# symbol.net
KiCad netlist of a schematic drawn in Altium Designer
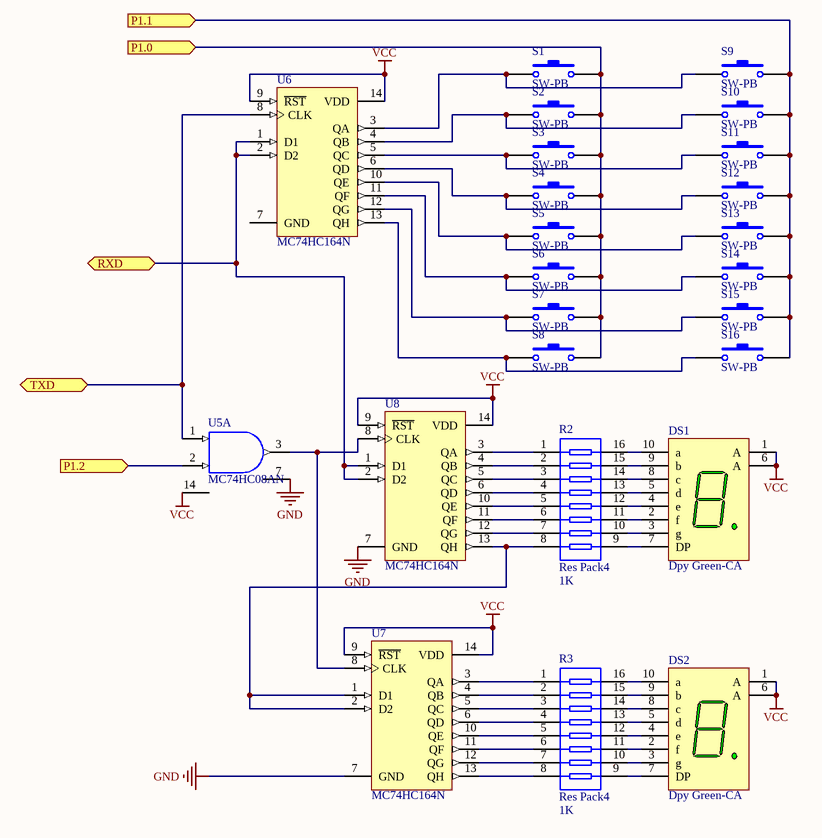
[diagram p0: 显示及键盘电路symbol.SchDoc]

(export (version "E")
  (design (tool "Eeschema 10.0.6"))
  (components
    (comp (ref "DS1")
      (value "Dpy Green-CA")
      (footprint "A")
      (description "7.62 mm Black Surface Green 7-Segment Display: CA, RH DP")
      (fields (field (name "PUBLISHER") "Altium Limited"))
      (libsource (lib "Miscellaneous Devices") (part "Dpy Green-CA"))
    )
    (comp (ref "DS2")
      (value "Dpy Green-CA")
      (footprint "A")
      (description "7.62 mm Black Surface Green 7-Segment Display: CA, RH DP")
      (fields (field (name "PUBLISHER") "Altium Limited"))
      (libsource (lib "Miscellaneous Devices") (part "Dpy Green-CA"))
    )
    (comp (ref "R2")
      (value "Res Pack4")
      (footprint "SSOP16_N")
      (description "Isolated Resistor Network")
      (fields (field (name "ALTIUM_VALUE") "1K") (field (name "PUBLISHER") "Altium Limited"))
      (libsource (lib "Miscellaneous Devices") (part "Res Pack4"))
    )
    (comp (ref "R3")
      (value "Res Pack4")
      (footprint "SSOP16_N")
      (description "Isolated Resistor Network")
      (fields (field (name "ALTIUM_VALUE") "1K") (field (name "PUBLISHER") "Altium Limited"))
      (libsource (lib "Miscellaneous Devices") (part "Res Pack4"))
    )
    (comp (ref "S1")
      (value "SW-PB")
      (footprint "SPST-2")
      (description "Switch")
      (fields (field (name "PUBLISHER") "Altium Limited"))
      (libsource (lib "Miscellaneous Devices") (part "SW-PB"))
    )
    (comp (ref "S2")
      (value "SW-PB")
      (footprint "SPST-2")
      (description "Switch")
      (fields (field (name "PUBLISHER") "Altium Limited"))
      (libsource (lib "Miscellaneous Devices") (part "SW-PB"))
    )
    (comp (ref "S3")
      (value "SW-PB")
      (footprint "SPST-2")
      (description "Switch")
      (fields (field (name "PUBLISHER") "Altium Limited"))
      (libsource (lib "Miscellaneous Devices") (part "SW-PB"))
    )
    (comp (ref "S4")
      (value "SW-PB")
      (footprint "SPST-2")
      (description "Switch")
      (fields (field (name "PUBLISHER") "Altium Limited"))
      (libsource (lib "Miscellaneous Devices") (part "SW-PB"))
    )
    (comp (ref "S5")
      (value "SW-PB")
      (footprint "SPST-2")
      (description "Switch")
      (fields (field (name "PUBLISHER") "Altium Limited"))
      (libsource (lib "Miscellaneous Devices") (part "SW-PB"))
    )
    (comp (ref "S6")
      (value "SW-PB")
      (footprint "SPST-2")
      (description "Switch")
      (fields (field (name "PUBLISHER") "Altium Limited"))
      (libsource (lib "Miscellaneous Devices") (part "SW-PB"))
    )
    (comp (ref "S7")
      (value "SW-PB")
      (footprint "SPST-2")
      (description "Switch")
      (fields (field (name "PUBLISHER") "Altium Limited"))
      (libsource (lib "Miscellaneous Devices") (part "SW-PB"))
    )
    (comp (ref "S8")
      (value "SW-PB")
      (footprint "SPST-2")
      (description "Switch")
      (fields (field (name "PUBLISHER") "Altium Limited"))
      (libsource (lib "Miscellaneous Devices") (part "SW-PB"))
    )
    (comp (ref "S9")
      (value "SW-PB")
      (footprint "SPST-2")
      (description "Switch")
      (fields (field (name "PUBLISHER") "Altium Limited"))
      (libsource (lib "Miscellaneous Devices") (part "SW-PB"))
    )
    (comp (ref "S10")
      (value "SW-PB")
      (footprint "SPST-2")
      (description "Switch")
      (fields (field (name "PUBLISHER") "Altium Limited"))
      (libsource (lib "Miscellaneous Devices") (part "SW-PB"))
    )
    (comp (ref "S11")
      (value "SW-PB")
      (footprint "SPST-2")
      (description "Switch")
      (fields (field (name "PUBLISHER") "Altium Limited"))
      (libsource (lib "Miscellaneous Devices") (part "SW-PB"))
    )
    (comp (ref "S12")
      (value "SW-PB")
      (footprint "SPST-2")
      (description "Switch")
      (fields (field (name "PUBLISHER") "Altium Limited"))
      (libsource (lib "Miscellaneous Devices") (part "SW-PB"))
    )
    (comp (ref "S13")
      (value "SW-PB")
      (footprint "SPST-2")
      (description "Switch")
      (fields (field (name "PUBLISHER") "Altium Limited"))
      (libsource (lib "Miscellaneous Devices") (part "SW-PB"))
    )
    (comp (ref "S14")
      (value "SW-PB")
      (footprint "SPST-2")
      (description "Switch")
      (fields (field (name "PUBLISHER") "Altium Limited"))
      (libsource (lib "Miscellaneous Devices") (part "SW-PB"))
    )
    (comp (ref "S15")
      (value "SW-PB")
      (footprint "SPST-2")
      (description "Switch")
      (fields (field (name "PUBLISHER") "Altium Limited"))
      (libsource (lib "Miscellaneous Devices") (part "SW-PB"))
    )
    (comp (ref "S16")
      (value "SW-PB")
      (footprint "SPST-2")
      (description "Switch")
      (fields (field (name "PUBLISHER") "Altium Limited"))
      (libsource (lib "Miscellaneous Devices") (part "SW-PB"))
    )
    (comp (ref "U5")
      (value "MC74HC08AN")
      (footprint "646-06")
      (description "Quad 2-Input AND Gate")
      (fields (field (name "PUBLISHER") "Altium Limited"))
      (libsource (lib "Motorola Logic Gate") (part "MC74HC08AN"))
    )
    (comp (ref "U6")
      (value "MC74HC164N")
      (footprint "646-06")
      (description "8-Bit Serial-Input/Parallel-Output Shift Register")
      (fields (field (name "PUBLISHER") "Altium Limited"))
      (libsource (lib "Motorola Logic Register") (part "MC74HC164N"))
    )
    (comp (ref "U7")
      (value "MC74HC164N")
      (footprint "646-06")
      (description "8-Bit Serial-Input/Parallel-Output Shift Register")
      (fields (field (name "PUBLISHER") "Altium Limited"))
      (libsource (lib "Motorola Logic Register") (part "MC74HC164N"))
    )
    (comp (ref "U8")
      (value "MC74HC164N")
      (footprint "646-06")
      (description "8-Bit Serial-Input/Parallel-Output Shift Register")
      (fields (field (name "PUBLISHER") "Altium Limited"))
      (libsource (lib "Motorola Logic Register") (part "MC74HC164N"))
    )
  )
  (nets
    (net (code "1") (name "/P1.0") (class "Default")
      (node (ref "S1") (pin "2") (pinfunction "2_2") (pintype "passive"))
      (node (ref "S2") (pin "2") (pinfunction "2_2") (pintype "passive"))
      (node (ref "S3") (pin "2") (pinfunction "2_2") (pintype "passive"))
      (node (ref "S4") (pin "2") (pinfunction "2_2") (pintype "passive"))
      (node (ref "S5") (pin "2") (pinfunction "2_2") (pintype "passive"))
      (node (ref "S6") (pin "2") (pinfunction "2_2") (pintype "passive"))
      (node (ref "S7") (pin "2") (pinfunction "2_2") (pintype "passive"))
      (node (ref "S8") (pin "2") (pinfunction "2_2") (pintype "passive"))
    )
    (net (code "2") (name "/P1.1") (class "Default")
      (node (ref "S10") (pin "2") (pinfunction "2_2") (pintype "passive"))
      (node (ref "S11") (pin "2") (pinfunction "2_2") (pintype "passive"))
      (node (ref "S12") (pin "2") (pinfunction "2_2") (pintype "passive"))
      (node (ref "S13") (pin "2") (pinfunction "2_2") (pintype "passive"))
      (node (ref "S14") (pin "2") (pinfunction "2_2") (pintype "passive"))
      (node (ref "S15") (pin "2") (pinfunction "2_2") (pintype "passive"))
      (node (ref "S16") (pin "2") (pinfunction "2_2") (pintype "passive"))
      (node (ref "S9") (pin "2") (pinfunction "2_2") (pintype "passive"))
    )
    (net (code "3") (name "/P1.2") (class "Default")
      (node (ref "U5") (pin "2") (pinfunction "B_2") (pintype "input"))
    )
    (net (code "4") (name "/RXD") (class "Default")
      (node (ref "U6") (pin "1") (pinfunction "D1_1") (pintype "input"))
      (node (ref "U6") (pin "2") (pinfunction "D2_2") (pintype "input"))
      (node (ref "U8") (pin "1") (pinfunction "D1_1") (pintype "input"))
      (node (ref "U8") (pin "2") (pinfunction "D2_2") (pintype "input"))
    )
    (net (code "5") (name "/TXD") (class "Default")
      (node (ref "U5") (pin "1") (pinfunction "A_1") (pintype "input"))
      (node (ref "U6") (pin "8") (pinfunction "CLK_8") (pintype "input"))
    )
    (net (code "6") (name "GND") (class "Default")
      (node (ref "U5") (pin "7") (pinfunction "GND_7") (pintype "power_in"))
      (node (ref "U7") (pin "7") (pinfunction "GND_7") (pintype "power_in"))
      (node (ref "U8") (pin "7") (pinfunction "GND_7") (pintype "power_in"))
    )
    (net (code "7") (name "Net-(DS1-DP)") (class "Default")
      (node (ref "DS1") (pin "7") (pinfunction "DP_7") (pintype "passive"))
      (node (ref "R2") (pin "9") (pinfunction "9_9") (pintype "passive"))
    )
    (net (code "8") (name "Net-(DS1-a)") (class "Default")
      (node (ref "DS1") (pin "10") (pinfunction "a_10") (pintype "passive"))
      (node (ref "R2") (pin "16") (pinfunction "16_16") (pintype "passive"))
    )
    (net (code "9") (name "Net-(DS1-b)") (class "Default")
      (node (ref "DS1") (pin "9") (pinfunction "b_9") (pintype "passive"))
      (node (ref "R2") (pin "15") (pinfunction "15_15") (pintype "passive"))
    )
    (net (code "10") (name "Net-(DS1-c)") (class "Default")
      (node (ref "DS1") (pin "8") (pinfunction "c_8") (pintype "passive"))
      (node (ref "R2") (pin "14") (pinfunction "14_14") (pintype "passive"))
    )
    (net (code "11") (name "Net-(DS1-d)") (class "Default")
      (node (ref "DS1") (pin "5") (pinfunction "d_5") (pintype "passive"))
      (node (ref "R2") (pin "13") (pinfunction "13_13") (pintype "passive"))
    )
    (net (code "12") (name "Net-(DS1-e)") (class "Default")
      (node (ref "DS1") (pin "4") (pinfunction "e_4") (pintype "passive"))
      (node (ref "R2") (pin "12") (pinfunction "12_12") (pintype "passive"))
    )
    (net (code "13") (name "Net-(DS1-f)") (class "Default")
      (node (ref "DS1") (pin "2") (pinfunction "f_2") (pintype "passive"))
      (node (ref "R2") (pin "11") (pinfunction "11_11") (pintype "passive"))
    )
    (net (code "14") (name "Net-(DS1-g)") (class "Default")
      (node (ref "DS1") (pin "3") (pinfunction "g_3") (pintype "passive"))
      (node (ref "R2") (pin "10") (pinfunction "10_10") (pintype "passive"))
    )
    (net (code "15") (name "Net-(DS2-DP)") (class "Default")
      (node (ref "DS2") (pin "7") (pinfunction "DP_7") (pintype "passive"))
      (node (ref "R3") (pin "9") (pinfunction "9_9") (pintype "passive"))
    )
    (net (code "16") (name "Net-(DS2-a)") (class "Default")
      (node (ref "DS2") (pin "10") (pinfunction "a_10") (pintype "passive"))
      (node (ref "R3") (pin "16") (pinfunction "16_16") (pintype "passive"))
    )
    (net (code "17") (name "Net-(DS2-b)") (class "Default")
      (node (ref "DS2") (pin "9") (pinfunction "b_9") (pintype "passive"))
      (node (ref "R3") (pin "15") (pinfunction "15_15") (pintype "passive"))
    )
    (net (code "18") (name "Net-(DS2-c)") (class "Default")
      (node (ref "DS2") (pin "8") (pinfunction "c_8") (pintype "passive"))
      (node (ref "R3") (pin "14") (pinfunction "14_14") (pintype "passive"))
    )
    (net (code "19") (name "Net-(DS2-d)") (class "Default")
      (node (ref "DS2") (pin "5") (pinfunction "d_5") (pintype "passive"))
      (node (ref "R3") (pin "13") (pinfunction "13_13") (pintype "passive"))
    )
    (net (code "20") (name "Net-(DS2-e)") (class "Default")
      (node (ref "DS2") (pin "4") (pinfunction "e_4") (pintype "passive"))
      (node (ref "R3") (pin "12") (pinfunction "12_12") (pintype "passive"))
    )
    (net (code "21") (name "Net-(DS2-f)") (class "Default")
      (node (ref "DS2") (pin "2") (pinfunction "f_2") (pintype "passive"))
      (node (ref "R3") (pin "11") (pinfunction "11_11") (pintype "passive"))
    )
    (net (code "22") (name "Net-(DS2-g)") (class "Default")
      (node (ref "DS2") (pin "3") (pinfunction "g_3") (pintype "passive"))
      (node (ref "R3") (pin "10") (pinfunction "10_10") (pintype "passive"))
    )
    (net (code "23") (name "Net-(U5A-Y)") (class "Default")
      (node (ref "U5") (pin "3") (pinfunction "Y_3") (pintype "output"))
      (node (ref "U7") (pin "8") (pinfunction "CLK_8") (pintype "input"))
      (node (ref "U8") (pin "8") (pinfunction "CLK_8") (pintype "input"))
    )
    (net (code "24") (name "Net-(U6-QA)") (class "Default")
      (node (ref "S1") (pin "1") (pinfunction "1_1") (pintype "passive"))
      (node (ref "S9") (pin "1") (pinfunction "1_1") (pintype "passive"))
      (node (ref "U6") (pin "3") (pinfunction "QA_3") (pintype "output"))
    )
    (net (code "25") (name "Net-(U6-QB)") (class "Default")
      (node (ref "S10") (pin "1") (pinfunction "1_1") (pintype "passive"))
      (node (ref "S2") (pin "1") (pinfunction "1_1") (pintype "passive"))
      (node (ref "U6") (pin "4") (pinfunction "QB_4") (pintype "output"))
    )
    (net (code "26") (name "Net-(U6-QC)") (class "Default")
      (node (ref "S11") (pin "1") (pinfunction "1_1") (pintype "passive"))
      (node (ref "S3") (pin "1") (pinfunction "1_1") (pintype "passive"))
      (node (ref "U6") (pin "5") (pinfunction "QC_5") (pintype "output"))
    )
    (net (code "27") (name "Net-(U6-QD)") (class "Default")
      (node (ref "S12") (pin "1") (pinfunction "1_1") (pintype "passive"))
      (node (ref "S4") (pin "1") (pinfunction "1_1") (pintype "passive"))
      (node (ref "U6") (pin "6") (pinfunction "QD_6") (pintype "output"))
    )
    (net (code "28") (name "Net-(U6-QE)") (class "Default")
      (node (ref "S13") (pin "1") (pinfunction "1_1") (pintype "passive"))
      (node (ref "S5") (pin "1") (pinfunction "1_1") (pintype "passive"))
      (node (ref "U6") (pin "10") (pinfunction "QE_10") (pintype "output"))
    )
    (net (code "29") (name "Net-(U6-QF)") (class "Default")
      (node (ref "S14") (pin "1") (pinfunction "1_1") (pintype "passive"))
      (node (ref "S6") (pin "1") (pinfunction "1_1") (pintype "passive"))
      (node (ref "U6") (pin "11") (pinfunction "QF_11") (pintype "output"))
    )
    (net (code "30") (name "Net-(U6-QG)") (class "Default")
      (node (ref "S15") (pin "1") (pinfunction "1_1") (pintype "passive"))
      (node (ref "S7") (pin "1") (pinfunction "1_1") (pintype "passive"))
      (node (ref "U6") (pin "12") (pinfunction "QG_12") (pintype "output"))
    )
    (net (code "31") (name "Net-(U6-QH)") (class "Default")
      (node (ref "S16") (pin "1") (pinfunction "1_1") (pintype "passive"))
      (node (ref "S8") (pin "1") (pinfunction "1_1") (pintype "passive"))
      (node (ref "U6") (pin "13") (pinfunction "QH_13") (pintype "output"))
    )
    (net (code "32") (name "Net-(U7-D1)") (class "Default")
      (node (ref "R2") (pin "8") (pinfunction "8_8") (pintype "passive"))
      (node (ref "U7") (pin "1") (pinfunction "D1_1") (pintype "input"))
      (node (ref "U7") (pin "2") (pinfunction "D2_2") (pintype "input"))
      (node (ref "U8") (pin "13") (pinfunction "QH_13") (pintype "output"))
    )
    (net (code "33") (name "Net-(U7-QA)") (class "Default")
      (node (ref "R3") (pin "1") (pinfunction "1_1") (pintype "passive"))
      (node (ref "U7") (pin "3") (pinfunction "QA_3") (pintype "output"))
    )
    (net (code "34") (name "Net-(U7-QB)") (class "Default")
      (node (ref "R3") (pin "2") (pinfunction "2_2") (pintype "passive"))
      (node (ref "U7") (pin "4") (pinfunction "QB_4") (pintype "output"))
    )
    (net (code "35") (name "Net-(U7-QC)") (class "Default")
      (node (ref "R3") (pin "3") (pinfunction "3_3") (pintype "passive"))
      (node (ref "U7") (pin "5") (pinfunction "QC_5") (pintype "output"))
    )
    (net (code "36") (name "Net-(U7-QD)") (class "Default")
      (node (ref "R3") (pin "4") (pinfunction "4_4") (pintype "passive"))
      (node (ref "U7") (pin "6") (pinfunction "QD_6") (pintype "output"))
    )
    (net (code "37") (name "Net-(U7-QE)") (class "Default")
      (node (ref "R3") (pin "5") (pinfunction "5_5") (pintype "passive"))
      (node (ref "U7") (pin "10") (pinfunction "QE_10") (pintype "output"))
    )
    (net (code "38") (name "Net-(U7-QF)") (class "Default")
      (node (ref "R3") (pin "6") (pinfunction "6_6") (pintype "passive"))
      (node (ref "U7") (pin "11") (pinfunction "QF_11") (pintype "output"))
    )
    (net (code "39") (name "Net-(U7-QG)") (class "Default")
      (node (ref "R3") (pin "7") (pinfunction "7_7") (pintype "passive"))
      (node (ref "U7") (pin "12") (pinfunction "QG_12") (pintype "output"))
    )
    (net (code "40") (name "Net-(U7-QH)") (class "Default")
      (node (ref "R3") (pin "8") (pinfunction "8_8") (pintype "passive"))
      (node (ref "U7") (pin "13") (pinfunction "QH_13") (pintype "output"))
    )
    (net (code "41") (name "Net-(U8-QA)") (class "Default")
      (node (ref "R2") (pin "1") (pinfunction "1_1") (pintype "passive"))
      (node (ref "U8") (pin "3") (pinfunction "QA_3") (pintype "output"))
    )
    (net (code "42") (name "Net-(U8-QB)") (class "Default")
      (node (ref "R2") (pin "2") (pinfunction "2_2") (pintype "passive"))
      (node (ref "U8") (pin "4") (pinfunction "QB_4") (pintype "output"))
    )
    (net (code "43") (name "Net-(U8-QC)") (class "Default")
      (node (ref "R2") (pin "3") (pinfunction "3_3") (pintype "passive"))
      (node (ref "U8") (pin "5") (pinfunction "QC_5") (pintype "output"))
    )
    (net (code "44") (name "Net-(U8-QD)") (class "Default")
      (node (ref "R2") (pin "4") (pinfunction "4_4") (pintype "passive"))
      (node (ref "U8") (pin "6") (pinfunction "QD_6") (pintype "output"))
    )
    (net (code "45") (name "Net-(U8-QE)") (class "Default")
      (node (ref "R2") (pin "5") (pinfunction "5_5") (pintype "passive"))
      (node (ref "U8") (pin "10") (pinfunction "QE_10") (pintype "output"))
    )
    (net (code "46") (name "Net-(U8-QF)") (class "Default")
      (node (ref "R2") (pin "6") (pinfunction "6_6") (pintype "passive"))
      (node (ref "U8") (pin "11") (pinfunction "QF_11") (pintype "output"))
    )
    (net (code "47") (name "Net-(U8-QG)") (class "Default")
      (node (ref "R2") (pin "7") (pinfunction "7_7") (pintype "passive"))
      (node (ref "U8") (pin "12") (pinfunction "QG_12") (pintype "output"))
    )
    (net (code "48") (name "VCC") (class "Default")
      (node (ref "DS1") (pin "1") (pinfunction "A_1") (pintype "passive"))
      (node (ref "DS1") (pin "6") (pinfunction "A_6") (pintype "passive"))
      (node (ref "DS2") (pin "1") (pinfunction "A_1") (pintype "passive"))
      (node (ref "DS2") (pin "6") (pinfunction "A_6") (pintype "passive"))
      (node (ref "U5") (pin "14") (pinfunction "VDD_14") (pintype "power_in"))
      (node (ref "U6") (pin "14") (pinfunction "VDD_14") (pintype "power_in"))
      (node (ref "U6") (pin "9") (pinfunction "~{RST}_9") (pintype "input"))
      (node (ref "U7") (pin "14") (pinfunction "VDD_14") (pintype "power_in"))
      (node (ref "U7") (pin "9") (pinfunction "~{RST}_9") (pintype "input"))
      (node (ref "U8") (pin "14") (pinfunction "VDD_14") (pintype "power_in"))
      (node (ref "U8") (pin "9") (pinfunction "~{RST}_9") (pintype "input"))
    )
    (net (code "49") (name "unconnected-(U6-GND-Pad7)") (class "Default")
      (node (ref "U6") (pin "7") (pinfunction "GND_7") (pintype "power_in"))
    )
  )
)
